# MEP-_kol-4.net
KiCad netlist of a schematic drawn in EAGLE
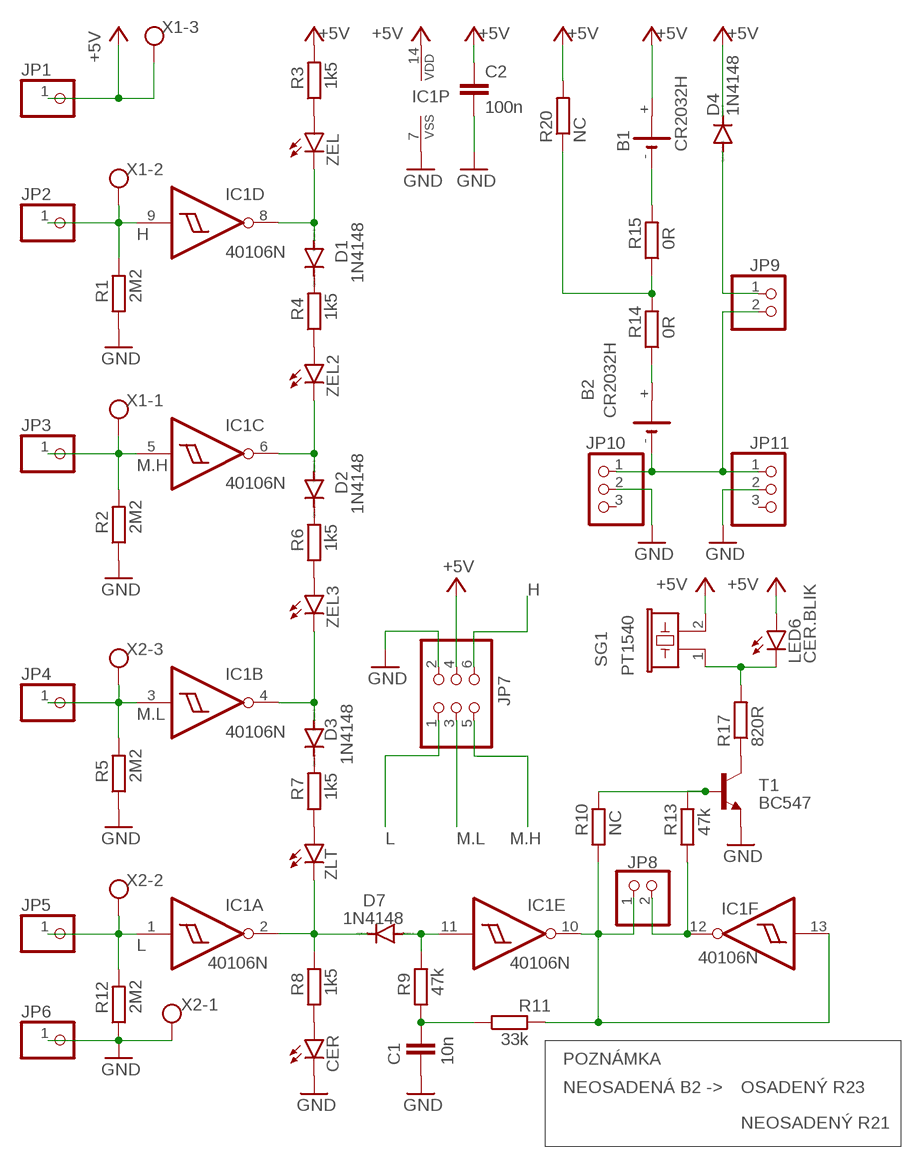
[diagram p0: schematic, sheet 1]

(export (version "E")
  (design (tool "Eeschema 10.0.6"))
  (components
    (comp (ref "B1")
      (value "CR2032H")
      (footprint "eagle-import:CR2032H")
      (libsource (lib "eagle-import") (part "CR2032H"))
    )
    (comp (ref "B2")
      (value "CR2032H")
      (footprint "eagle-import:CR2032H")
      (libsource (lib "eagle-import") (part "CR2032H"))
    )
    (comp (ref "C1")
      (value "10n")
      (footprint "eagle-import:C0805")
      (libsource (lib "eagle-import") (part "C-EUC0805"))
    )
    (comp (ref "C2")
      (value "100n")
      (footprint "eagle-import:C0805")
      (libsource (lib "eagle-import") (part "C-EUC0805"))
    )
    (comp (ref "CER")
      (value "LEDCHIP-LED0805")
      (footprint "eagle-import:CHIP-LED0805")
      (libsource (lib "eagle-import") (part "LEDCHIP-LED0805"))
    )
    (comp (ref "D1")
      (value "1N4148")
      (footprint "eagle-import:DO35-7")
      (libsource (lib "eagle-import") (part "1N4148DO35-7"))
    )
    (comp (ref "D2")
      (value "1N4148")
      (footprint "eagle-import:DO35-7")
      (libsource (lib "eagle-import") (part "1N4148DO35-7"))
    )
    (comp (ref "D3")
      (value "1N4148")
      (footprint "eagle-import:DO35-7")
      (libsource (lib "eagle-import") (part "1N4148DO35-7"))
    )
    (comp (ref "D4")
      (value "1N4148")
      (footprint "eagle-import:DO35-7")
      (libsource (lib "eagle-import") (part "1N4148DO35-7"))
    )
    (comp (ref "D7")
      (value "1N4148")
      (footprint "eagle-import:DO35-7")
      (libsource (lib "eagle-import") (part "1N4148DO35-7"))
    )
    (comp (ref "IC1")
      (value "40106N")
      (footprint "eagle-import:DIL14")
      (libsource (lib "eagle-import") (part "40106N"))
    )
    (comp (ref "JP1")
      (value "PINHD-1X1")
      (footprint "eagle-import:1X01")
      (libsource (lib "eagle-import") (part "PINHD-1X1"))
    )
    (comp (ref "JP2")
      (value "PINHD-1X1")
      (footprint "eagle-import:1X01")
      (libsource (lib "eagle-import") (part "PINHD-1X1"))
    )
    (comp (ref "JP3")
      (value "PINHD-1X1")
      (footprint "eagle-import:1X01")
      (libsource (lib "eagle-import") (part "PINHD-1X1"))
    )
    (comp (ref "JP4")
      (value "PINHD-1X1")
      (footprint "eagle-import:1X01")
      (libsource (lib "eagle-import") (part "PINHD-1X1"))
    )
    (comp (ref "JP5")
      (value "PINHD-1X1")
      (footprint "eagle-import:1X01")
      (libsource (lib "eagle-import") (part "PINHD-1X1"))
    )
    (comp (ref "JP6")
      (value "PINHD-1X1")
      (footprint "eagle-import:1X01")
      (libsource (lib "eagle-import") (part "PINHD-1X1"))
    )
    (comp (ref "JP7")
      (value "PINHD-2X3")
      (footprint "eagle-import:2X03")
      (libsource (lib "eagle-import") (part "PINHD-2X3"))
    )
    (comp (ref "JP8")
      (value "PINHD-1X2")
      (footprint "eagle-import:1X02")
      (libsource (lib "eagle-import") (part "PINHD-1X2"))
    )
    (comp (ref "JP9")
      (value "PINHD-1X2")
      (footprint "eagle-import:1X02")
      (libsource (lib "eagle-import") (part "PINHD-1X2"))
    )
    (comp (ref "JP10")
      (value "PINHD-1X3")
      (footprint "eagle-import:1X03")
      (libsource (lib "eagle-import") (part "PINHD-1X3"))
    )
    (comp (ref "JP11")
      (value "PINHD-1X3")
      (footprint "eagle-import:1X03")
      (libsource (lib "eagle-import") (part "PINHD-1X3"))
    )
    (comp (ref "LED6")
      (value "CER.BLIK")
      (footprint "eagle-import:CHIP-LED0805")
      (libsource (lib "eagle-import") (part "LEDCHIP-LED0805"))
    )
    (comp (ref "R1")
      (value "2M2")
      (footprint "eagle-import:R0805")
      (libsource (lib "eagle-import") (part "R-EU_R0805"))
    )
    (comp (ref "R2")
      (value "2M2")
      (footprint "eagle-import:R0805")
      (libsource (lib "eagle-import") (part "R-EU_R0805"))
    )
    (comp (ref "R3")
      (value "1k5")
      (footprint "eagle-import:R0805")
      (libsource (lib "eagle-import") (part "R-EU_R0805"))
    )
    (comp (ref "R4")
      (value "1k5")
      (footprint "eagle-import:R0805")
      (libsource (lib "eagle-import") (part "R-EU_R0805"))
    )
    (comp (ref "R5")
      (value "2M2")
      (footprint "eagle-import:R0805")
      (libsource (lib "eagle-import") (part "R-EU_R0805"))
    )
    (comp (ref "R6")
      (value "1k5")
      (footprint "eagle-import:R0805")
      (libsource (lib "eagle-import") (part "R-EU_R0805"))
    )
    (comp (ref "R7")
      (value "1k5")
      (footprint "eagle-import:R0805")
      (libsource (lib "eagle-import") (part "R-EU_R0805"))
    )
    (comp (ref "R8")
      (value "1k5")
      (footprint "eagle-import:R0805")
      (libsource (lib "eagle-import") (part "R-EU_R0805"))
    )
    (comp (ref "R9")
      (value "47k")
      (footprint "eagle-import:R0805")
      (libsource (lib "eagle-import") (part "R-EU_R0805"))
    )
    (comp (ref "R10")
      (value "NC")
      (footprint "eagle-import:R0805")
      (libsource (lib "eagle-import") (part "R-EU_R0805"))
    )
    (comp (ref "R11")
      (value "33k")
      (footprint "eagle-import:R0805")
      (libsource (lib "eagle-import") (part "R-EU_R0805"))
    )
    (comp (ref "R12")
      (value "2M2")
      (footprint "eagle-import:R0805")
      (libsource (lib "eagle-import") (part "R-EU_R0805"))
    )
    (comp (ref "R13")
      (value "47k")
      (footprint "eagle-import:R0805")
      (libsource (lib "eagle-import") (part "R-EU_R0805"))
    )
    (comp (ref "R14")
      (value "0R")
      (footprint "eagle-import:R0805")
      (libsource (lib "eagle-import") (part "R-EU_R0805"))
    )
    (comp (ref "R15")
      (value "0R")
      (footprint "eagle-import:R0805")
      (libsource (lib "eagle-import") (part "R-EU_R0805"))
    )
    (comp (ref "R17")
      (value "820R")
      (footprint "eagle-import:R0805")
      (libsource (lib "eagle-import") (part "R-EU_R0805"))
    )
    (comp (ref "R20")
      (value "NC")
      (footprint "eagle-import:R0805")
      (libsource (lib "eagle-import") (part "R-EU_R0805"))
    )
    (comp (ref "SG1")
      (value "PT1540")
      (footprint "eagle-import:EFBRD22C41")
      (libsource (lib "eagle-import") (part "EFB?RD22C41"))
    )
    (comp (ref "T1")
      (value "BC547")
      (footprint "eagle-import:SOT23-BEC")
      (libsource (lib "eagle-import") (part "-NPN-SOT23-BECBC847"))
    )
    (comp (ref "X1")
      (value "AK500/3")
      (footprint "eagle-import:AK500_3")
      (libsource (lib "eagle-import") (part "AK500/3"))
    )
    (comp (ref "X2")
      (value "AK500/3")
      (footprint "eagle-import:AK500_3")
      (libsource (lib "eagle-import") (part "AK500/3"))
    )
    (comp (ref "ZEL")
      (value "LEDCHIP-LED0805")
      (footprint "eagle-import:CHIP-LED0805")
      (libsource (lib "eagle-import") (part "LEDCHIP-LED0805"))
    )
    (comp (ref "ZEL2")
      (value "LEDCHIP-LED0805")
      (footprint "eagle-import:CHIP-LED0805")
      (libsource (lib "eagle-import") (part "LEDCHIP-LED0805"))
    )
    (comp (ref "ZEL3")
      (value "LEDCHIP-LED0805")
      (footprint "eagle-import:CHIP-LED0805")
      (libsource (lib "eagle-import") (part "LEDCHIP-LED0805"))
    )
    (comp (ref "ZLT")
      (value "LEDCHIP-LED0805")
      (footprint "eagle-import:CHIP-LED0805")
      (libsource (lib "eagle-import") (part "LEDCHIP-LED0805"))
    )
  )
  (nets
    (net (code "1") (name "+5V") (class "Default")
      (node (ref "B1") (pin "+") (pinfunction "+_+") (pintype "passive"))
      (node (ref "C2") (pin "1") (pinfunction "1_1") (pintype "passive"))
      (node (ref "D4") (pin "C") (pinfunction "C_C") (pintype "passive"))
      (node (ref "IC1") (pin "14") (pinfunction "VDD_14") (pintype "power_in"))
      (node (ref "JP1") (pin "1") (pinfunction "1_1") (pintype "passive"))
      (node (ref "JP7") (pin "4") (pinfunction "4_4") (pintype "passive"))
      (node (ref "LED6") (pin "A") (pinfunction "A_A") (pintype "passive"))
      (node (ref "R20") (pin "2") (pinfunction "2_2") (pintype "passive"))
      (node (ref "R3") (pin "2") (pinfunction "2_2") (pintype "passive"))
      (node (ref "SG1") (pin "2") (pinfunction "2_2") (pintype "passive"))
      (node (ref "X1") (pin "3") (pinfunction "KL_3") (pintype "passive"))
    )
    (net (code "2") (name "/H") (class "Default")
      (node (ref "IC1") (pin "9") (pinfunction "I_9") (pintype "input"))
      (node (ref "JP2") (pin "1") (pinfunction "1_1") (pintype "passive"))
      (node (ref "JP7") (pin "6") (pinfunction "6_6") (pintype "passive"))
      (node (ref "R1") (pin "2") (pinfunction "2_2") (pintype "passive"))
      (node (ref "X1") (pin "2") (pinfunction "KL_2") (pintype "passive"))
    )
    (net (code "3") (name "/L") (class "Default")
      (node (ref "IC1") (pin "1") (pinfunction "I_1") (pintype "input"))
      (node (ref "JP5") (pin "1") (pinfunction "1_1") (pintype "passive"))
      (node (ref "JP7") (pin "1") (pinfunction "1_1") (pintype "passive"))
      (node (ref "R12") (pin "2") (pinfunction "2_2") (pintype "passive"))
      (node (ref "X2") (pin "2") (pinfunction "KL_2") (pintype "passive"))
    )
    (net (code "4") (name "/M.H") (class "Default")
      (node (ref "IC1") (pin "5") (pinfunction "I_5") (pintype "input"))
      (node (ref "JP3") (pin "1") (pinfunction "1_1") (pintype "passive"))
      (node (ref "JP7") (pin "5") (pinfunction "5_5") (pintype "passive"))
      (node (ref "R2") (pin "2") (pinfunction "2_2") (pintype "passive"))
      (node (ref "X1") (pin "1") (pinfunction "KL_1") (pintype "passive"))
    )
    (net (code "5") (name "/M.L") (class "Default")
      (node (ref "IC1") (pin "3") (pinfunction "I_3") (pintype "input"))
      (node (ref "JP4") (pin "1") (pinfunction "1_1") (pintype "passive"))
      (node (ref "JP7") (pin "3") (pinfunction "3_3") (pintype "passive"))
      (node (ref "R5") (pin "2") (pinfunction "2_2") (pintype "passive"))
      (node (ref "X2") (pin "3") (pinfunction "KL_3") (pintype "passive"))
    )
    (net (code "6") (name "GND") (class "Default")
      (node (ref "C1") (pin "2") (pinfunction "2_2") (pintype "passive"))
      (node (ref "C2") (pin "2") (pinfunction "2_2") (pintype "passive"))
      (node (ref "CER") (pin "C") (pinfunction "C_C") (pintype "passive"))
      (node (ref "IC1") (pin "7") (pinfunction "VSS_7") (pintype "power_in"))
      (node (ref "JP10") (pin "2") (pinfunction "2_2") (pintype "passive"))
      (node (ref "JP11") (pin "2") (pinfunction "2_2") (pintype "passive"))
      (node (ref "JP6") (pin "1") (pinfunction "1_1") (pintype "passive"))
      (node (ref "JP7") (pin "2") (pinfunction "2_2") (pintype "passive"))
      (node (ref "R1") (pin "1") (pinfunction "1_1") (pintype "passive"))
      (node (ref "R12") (pin "1") (pinfunction "1_1") (pintype "passive"))
      (node (ref "R2") (pin "1") (pinfunction "1_1") (pintype "passive"))
      (node (ref "R5") (pin "1") (pinfunction "1_1") (pintype "passive"))
      (node (ref "T1") (pin "E") (pinfunction "E_E") (pintype "passive"))
      (node (ref "X2") (pin "1") (pinfunction "KL_1") (pintype "passive"))
    )
    (net (code "7") (name "Net-(B1-Pad-)") (class "Default")
      (node (ref "B1") (pin "-") (pinfunction "-_-") (pintype "passive"))
      (node (ref "R15") (pin "2") (pinfunction "2_2") (pintype "passive"))
    )
    (net (code "8") (name "Net-(B2-Pad+)") (class "Default")
      (node (ref "B2") (pin "+") (pinfunction "+_+") (pintype "passive"))
      (node (ref "R14") (pin "1") (pinfunction "1_1") (pintype "passive"))
    )
    (net (code "9") (name "Net-(B2-Pad-)") (class "Default")
      (node (ref "B2") (pin "-") (pinfunction "-_-") (pintype "passive"))
      (node (ref "JP10") (pin "1") (pinfunction "1_1") (pintype "passive"))
      (node (ref "JP11") (pin "1") (pinfunction "1_1") (pintype "passive"))
      (node (ref "JP9") (pin "2") (pinfunction "2_2") (pintype "passive"))
    )
    (net (code "10") (name "Net-(C1-Pad1)") (class "Default")
      (node (ref "C1") (pin "1") (pinfunction "1_1") (pintype "passive"))
      (node (ref "R11") (pin "1") (pinfunction "1_1") (pintype "passive"))
      (node (ref "R9") (pin "1") (pinfunction "1_1") (pintype "passive"))
    )
    (net (code "11") (name "Net-(CER-PadA)") (class "Default")
      (node (ref "CER") (pin "A") (pinfunction "A_A") (pintype "passive"))
      (node (ref "R8") (pin "1") (pinfunction "1_1") (pintype "passive"))
    )
    (net (code "12") (name "Net-(D1-PadC)") (class "Default")
      (node (ref "D1") (pin "C") (pinfunction "C_C") (pintype "passive"))
      (node (ref "R4") (pin "2") (pinfunction "2_2") (pintype "passive"))
    )
    (net (code "13") (name "Net-(D2-PadC)") (class "Default")
      (node (ref "D2") (pin "C") (pinfunction "C_C") (pintype "passive"))
      (node (ref "R6") (pin "2") (pinfunction "2_2") (pintype "passive"))
    )
    (net (code "14") (name "Net-(D3-PadC)") (class "Default")
      (node (ref "D3") (pin "C") (pinfunction "C_C") (pintype "passive"))
      (node (ref "R7") (pin "2") (pinfunction "2_2") (pintype "passive"))
    )
    (net (code "15") (name "Net-(D4-PadA)") (class "Default")
      (node (ref "D4") (pin "A") (pinfunction "A_A") (pintype "passive"))
      (node (ref "JP9") (pin "1") (pinfunction "1_1") (pintype "passive"))
    )
    (net (code "16") (name "Net-(IC1A-O)") (class "Default")
      (node (ref "D7") (pin "C") (pinfunction "C_C") (pintype "passive"))
      (node (ref "IC1") (pin "2") (pinfunction "O_2") (pintype "output"))
      (node (ref "R8") (pin "2") (pinfunction "2_2") (pintype "passive"))
      (node (ref "ZLT") (pin "C") (pinfunction "C_C") (pintype "passive"))
    )
    (net (code "17") (name "Net-(IC1B-O)") (class "Default")
      (node (ref "D3") (pin "A") (pinfunction "A_A") (pintype "passive"))
      (node (ref "IC1") (pin "4") (pinfunction "O_4") (pintype "output"))
      (node (ref "ZEL3") (pin "C") (pinfunction "C_C") (pintype "passive"))
    )
    (net (code "18") (name "Net-(IC1C-O)") (class "Default")
      (node (ref "D2") (pin "A") (pinfunction "A_A") (pintype "passive"))
      (node (ref "IC1") (pin "6") (pinfunction "O_6") (pintype "output"))
      (node (ref "ZEL2") (pin "C") (pinfunction "C_C") (pintype "passive"))
    )
    (net (code "19") (name "Net-(IC1D-O)") (class "Default")
      (node (ref "D1") (pin "A") (pinfunction "A_A") (pintype "passive"))
      (node (ref "IC1") (pin "8") (pinfunction "O_8") (pintype "output"))
      (node (ref "ZEL") (pin "C") (pinfunction "C_C") (pintype "passive"))
    )
    (net (code "20") (name "Net-(IC1E-I)") (class "Default")
      (node (ref "D7") (pin "A") (pinfunction "A_A") (pintype "passive"))
      (node (ref "IC1") (pin "11") (pinfunction "I_11") (pintype "input"))
      (node (ref "R9") (pin "2") (pinfunction "2_2") (pintype "passive"))
    )
    (net (code "21") (name "Net-(IC1E-O)") (class "Default")
      (node (ref "IC1") (pin "10") (pinfunction "O_10") (pintype "output"))
      (node (ref "IC1") (pin "13") (pinfunction "I_13") (pintype "input"))
      (node (ref "JP8") (pin "1") (pinfunction "1_1") (pintype "passive"))
      (node (ref "R10") (pin "1") (pinfunction "1_1") (pintype "passive"))
      (node (ref "R11") (pin "2") (pinfunction "2_2") (pintype "passive"))
    )
    (net (code "22") (name "Net-(IC1F-O)") (class "Default")
      (node (ref "IC1") (pin "12") (pinfunction "O_12") (pintype "output"))
      (node (ref "JP8") (pin "2") (pinfunction "2_2") (pintype "passive"))
      (node (ref "R13") (pin "1") (pinfunction "1_1") (pintype "passive"))
    )
    (net (code "23") (name "Net-(LED6-PadC)") (class "Default")
      (node (ref "LED6") (pin "C") (pinfunction "C_C") (pintype "passive"))
      (node (ref "R17") (pin "2") (pinfunction "2_2") (pintype "passive"))
      (node (ref "SG1") (pin "1") (pinfunction "1_1") (pintype "passive"))
    )
    (net (code "24") (name "Net-(R3-Pad1)") (class "Default")
      (node (ref "R3") (pin "1") (pinfunction "1_1") (pintype "passive"))
      (node (ref "ZEL") (pin "A") (pinfunction "A_A") (pintype "passive"))
    )
    (net (code "25") (name "Net-(R4-Pad1)") (class "Default")
      (node (ref "R4") (pin "1") (pinfunction "1_1") (pintype "passive"))
      (node (ref "ZEL2") (pin "A") (pinfunction "A_A") (pintype "passive"))
    )
    (net (code "26") (name "Net-(R6-Pad1)") (class "Default")
      (node (ref "R6") (pin "1") (pinfunction "1_1") (pintype "passive"))
      (node (ref "ZEL3") (pin "A") (pinfunction "A_A") (pintype "passive"))
    )
    (net (code "27") (name "Net-(R7-Pad1)") (class "Default")
      (node (ref "R7") (pin "1") (pinfunction "1_1") (pintype "passive"))
      (node (ref "ZLT") (pin "A") (pinfunction "A_A") (pintype "passive"))
    )
    (net (code "28") (name "Net-(R10-Pad2)") (class "Default")
      (node (ref "R10") (pin "2") (pinfunction "2_2") (pintype "passive"))
      (node (ref "R13") (pin "2") (pinfunction "2_2") (pintype "passive"))
      (node (ref "T1") (pin "B") (pinfunction "B_B") (pintype "passive"))
    )
    (net (code "29") (name "Net-(R14-Pad2)") (class "Default")
      (node (ref "R14") (pin "2") (pinfunction "2_2") (pintype "passive"))
      (node (ref "R15") (pin "1") (pinfunction "1_1") (pintype "passive"))
      (node (ref "R20") (pin "1") (pinfunction "1_1") (pintype "passive"))
    )
    (net (code "30") (name "Net-(R17-Pad1)") (class "Default")
      (node (ref "R17") (pin "1") (pinfunction "1_1") (pintype "passive"))
      (node (ref "T1") (pin "C") (pinfunction "C_C") (pintype "passive"))
    )
    (net (code "31") (name "unconnected-(B1-+-Pad+@1)") (class "Default")
      (node (ref "B1") (pin "+@1") (pinfunction "+_+@1") (pintype "passive"))
    )
    (net (code "32") (name "unconnected-(B2-+-Pad+@1)") (class "Default")
      (node (ref "B2") (pin "+@1") (pinfunction "+_+@1") (pintype "passive"))
    )
    (net (code "33") (name "unconnected-(JP10-Pad3)") (class "Default")
      (node (ref "JP10") (pin "3") (pinfunction "3_3") (pintype "passive"))
    )
    (net (code "34") (name "unconnected-(JP11-Pad3)") (class "Default")
      (node (ref "JP11") (pin "3") (pinfunction "3_3") (pintype "passive"))
    )
  )
)
